# Main.net
KiCad netlist of a schematic drawn in Altium Designer
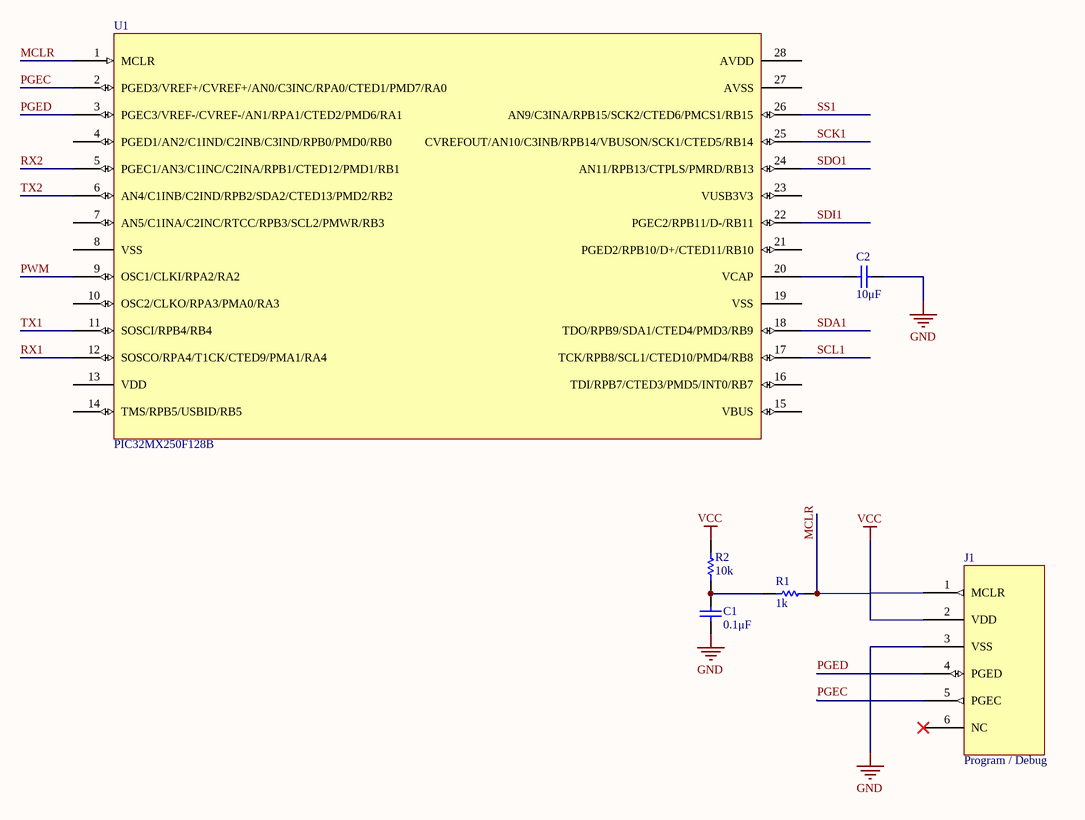
[diagram p0: Main.SchDoc]

(export (version "E")
  (design (tool "Eeschema 10.0.6"))
  (components
    (comp (ref "C1")
      (value "0.1μF")
      (footprint "RAD-0.3")
      (description "Capacitor")
      (fields (field (name "PUBLISHER") "Altium Limited"))
      (libsource (lib "Miscellaneous Devices") (part "Cap"))
    )
    (comp (ref "C2")
      (value "10μF")
      (footprint "RAD-0.3")
      (description "Capacitor")
      (fields (field (name "PUBLISHER") "Altium Limited"))
      (libsource (lib "Miscellaneous Devices") (part "Cap"))
    )
    (comp (ref "J1")
      (value "Program / Debug")
      (footprint "C-Grid III X6")
      (libsource (lib "Schlib") (part "ICSP"))
    )
    (comp (ref "R1")
      (value "1k")
      (footprint "AXIAL-0.3")
      (description "Resistor")
      (fields (field (name "PUBLISHER") "Altium Limited"))
      (libsource (lib "Miscellaneous Devices") (part "Res1"))
    )
    (comp (ref "R2")
      (value "10k")
      (footprint "AXIAL-0.3")
      (description "Resistor")
      (fields (field (name "PUBLISHER") "Altium Limited"))
      (libsource (lib "Miscellaneous Devices") (part "Res1"))
    )
    (comp (ref "U1")
      (value "PIC32MX250F128B")
      (description "Microcontrolleur")
      (libsource (lib "Schlib") (part "PIC32MX250F128B"))
    )
  )
  (nets
    (net (code "1") (name "/MCLR") (class "Default")
      (node (ref "J1") (pin "1") (pinfunction "MCLR_1") (pintype "output"))
      (node (ref "R1") (pin "1") (pinfunction "1_1") (pintype "passive"))
      (node (ref "U1") (pin "1") (pinfunction "MCLR_1") (pintype "input"))
    )
    (net (code "2") (name "/PGEC") (class "Default")
      (node (ref "J1") (pin "5") (pinfunction "PGEC_5") (pintype "output"))
      (node (ref "U1") (pin "2") (pinfunction "PGED3/VREF+/CVREF+/AN0/C3INC/RPA0/CTED1/PMD7/RA0_2") (pintype "bidirectional"))
    )
    (net (code "3") (name "/PGED") (class "Default")
      (node (ref "J1") (pin "4") (pinfunction "PGED_4") (pintype "bidirectional"))
      (node (ref "U1") (pin "3") (pinfunction "PGEC3/VREF-/CVREF-/AN1/RPA1/CTED2/PMD6/RA1_3") (pintype "bidirectional"))
    )
    (net (code "4") (name "/PWM") (class "Default")
      (node (ref "U1") (pin "9") (pinfunction "OSC1/CLKI/RPA2/RA2_9") (pintype "bidirectional"))
    )
    (net (code "5") (name "/RX1") (class "Default")
      (node (ref "U1") (pin "12") (pinfunction "SOSCO/RPA4/T1CK/CTED9/PMA1/RA4_12") (pintype "bidirectional"))
    )
    (net (code "6") (name "/RX2") (class "Default")
      (node (ref "U1") (pin "5") (pinfunction "PGEC1/AN3/C1INC/C2INA/RPB1/CTED12/PMD1/RB1_5") (pintype "bidirectional"))
    )
    (net (code "7") (name "/SCK1") (class "Default")
      (node (ref "U1") (pin "25") (pinfunction "CVREFOUT/AN10/C3INB/RPB14/VBUSON/SCK1/CTED5/RB14_25") (pintype "bidirectional"))
    )
    (net (code "8") (name "/SCL1") (class "Default")
      (node (ref "U1") (pin "17") (pinfunction "TCK/RPB8/SCL1/CTED10/PMD4/RB8_17") (pintype "bidirectional"))
    )
    (net (code "9") (name "/SDA1") (class "Default")
      (node (ref "U1") (pin "18") (pinfunction "TDO/RPB9/SDA1/CTED4/PMD3/RB9_18") (pintype "bidirectional"))
    )
    (net (code "10") (name "/SDI1") (class "Default")
      (node (ref "U1") (pin "22") (pinfunction "PGEC2/RPB11/D-/RB11_22") (pintype "bidirectional"))
    )
    (net (code "11") (name "/SDO1") (class "Default")
      (node (ref "U1") (pin "24") (pinfunction "AN11/RPB13/CTPLS/PMRD/RB13_24") (pintype "bidirectional"))
    )
    (net (code "12") (name "/SS1") (class "Default")
      (node (ref "U1") (pin "26") (pinfunction "AN9/C3INA/RPB15/SCK2/CTED6/PMCS1/RB15_26") (pintype "bidirectional"))
    )
    (net (code "13") (name "/TX1") (class "Default")
      (node (ref "U1") (pin "11") (pinfunction "SOSCI/RPB4/RB4_11") (pintype "bidirectional"))
    )
    (net (code "14") (name "/TX2") (class "Default")
      (node (ref "U1") (pin "6") (pinfunction "AN4/C1INB/C2IND/RPB2/SDA2/CTED13/PMD2/RB2_6") (pintype "bidirectional"))
    )
    (net (code "15") (name "GND") (class "Default")
      (node (ref "C1") (pin "1") (pinfunction "1_1") (pintype "passive"))
      (node (ref "C2") (pin "1") (pinfunction "1_1") (pintype "passive"))
      (node (ref "J1") (pin "3") (pinfunction "VSS_3") (pintype "power_in"))
    )
    (net (code "16") (name "Net-(C1-Pad2)") (class "Default")
      (node (ref "C1") (pin "2") (pinfunction "2_2") (pintype "passive"))
      (node (ref "R1") (pin "2") (pinfunction "2_2") (pintype "passive"))
      (node (ref "R2") (pin "2") (pinfunction "2_2") (pintype "passive"))
    )
    (net (code "17") (name "Net-(U1-VCAP)") (class "Default")
      (node (ref "C2") (pin "2") (pinfunction "2_2") (pintype "passive"))
      (node (ref "U1") (pin "20") (pinfunction "VCAP_20") (pintype "power_in"))
    )
    (net (code "18") (name "VCC") (class "Default")
      (node (ref "J1") (pin "2") (pinfunction "VDD_2") (pintype "power_in"))
      (node (ref "R2") (pin "1") (pinfunction "1_1") (pintype "passive"))
    )
    (net (code "19") (name "unconnected-(J1-NC-Pad6)") (class "Default")
      (node (ref "J1") (pin "6") (pinfunction "NC_6") (pintype "passive+no_connect"))
    )
    (net (code "20") (name "unconnected-(U1-AN5{slash}C1INA{slash}C2INC{slash}RTCC{slash}RPB3{slash}SCL2{slash}PMWR{slash}RB3-Pad7)") (class "Default")
      (node (ref "U1") (pin "7") (pinfunction "AN5/C1INA/C2INC/RTCC/RPB3/SCL2/PMWR/RB3_7") (pintype "bidirectional"))
    )
    (net (code "21") (name "unconnected-(U1-AVDD-Pad28)") (class "Default")
      (node (ref "U1") (pin "28") (pinfunction "AVDD_28") (pintype "power_in"))
    )
    (net (code "22") (name "unconnected-(U1-AVSS-Pad27)") (class "Default")
      (node (ref "U1") (pin "27") (pinfunction "AVSS_27") (pintype "power_in"))
    )
    (net (code "23") (name "unconnected-(U1-OSC2{slash}CLKO{slash}RPA3{slash}PMA0{slash}RA3-Pad10)") (class "Default")
      (node (ref "U1") (pin "10") (pinfunction "OSC2/CLKO/RPA3/PMA0/RA3_10") (pintype "bidirectional"))
    )
    (net (code "24") (name "unconnected-(U1-PGED1{slash}AN2{slash}C1IND{slash}C2INB{slash}C3IND{slash}RPB0{slash}PMD0{slash}RB0-Pad4)") (class "Default")
      (node (ref "U1") (pin "4") (pinfunction "PGED1/AN2/C1IND/C2INB/C3IND/RPB0/PMD0/RB0_4") (pintype "bidirectional"))
    )
    (net (code "25") (name "unconnected-(U1-PGED2{slash}RPB10{slash}D+{slash}CTED11{slash}RB10-Pad21)") (class "Default")
      (node (ref "U1") (pin "21") (pinfunction "PGED2/RPB10/D+/CTED11/RB10_21") (pintype "bidirectional"))
    )
    (net (code "26") (name "unconnected-(U1-TDI{slash}RPB7{slash}CTED3{slash}PMD5{slash}INT0{slash}RB7-Pad16)") (class "Default")
      (node (ref "U1") (pin "16") (pinfunction "TDI/RPB7/CTED3/PMD5/INT0/RB7_16") (pintype "bidirectional"))
    )
    (net (code "27") (name "unconnected-(U1-TMS{slash}RPB5{slash}USBID{slash}RB5-Pad14)") (class "Default")
      (node (ref "U1") (pin "14") (pinfunction "TMS/RPB5/USBID/RB5_14") (pintype "bidirectional"))
    )
    (net (code "28") (name "unconnected-(U1-VBUS-Pad15)") (class "Default")
      (node (ref "U1") (pin "15") (pinfunction "VBUS_15") (pintype "bidirectional"))
    )
    (net (code "29") (name "unconnected-(U1-VDD-Pad13)") (class "Default")
      (node (ref "U1") (pin "13") (pinfunction "VDD_13") (pintype "passive"))
    )
    (net (code "30") (name "unconnected-(U1-VSS-Pad8)") (class "Default")
      (node (ref "U1") (pin "8") (pinfunction "VSS_8") (pintype "power_in"))
    )
    (net (code "31") (name "unconnected-(U1-VSS-Pad19)") (class "Default")
      (node (ref "U1") (pin "19") (pinfunction "VSS_19") (pintype "power_in"))
    )
    (net (code "32") (name "unconnected-(U1-VUSB3V3-Pad23)") (class "Default")
      (node (ref "U1") (pin "23") (pinfunction "VUSB3V3_23") (pintype "bidirectional"))
    )
  )
)
